# Principal.net
KiCad netlist of a schematic drawn in EAGLE
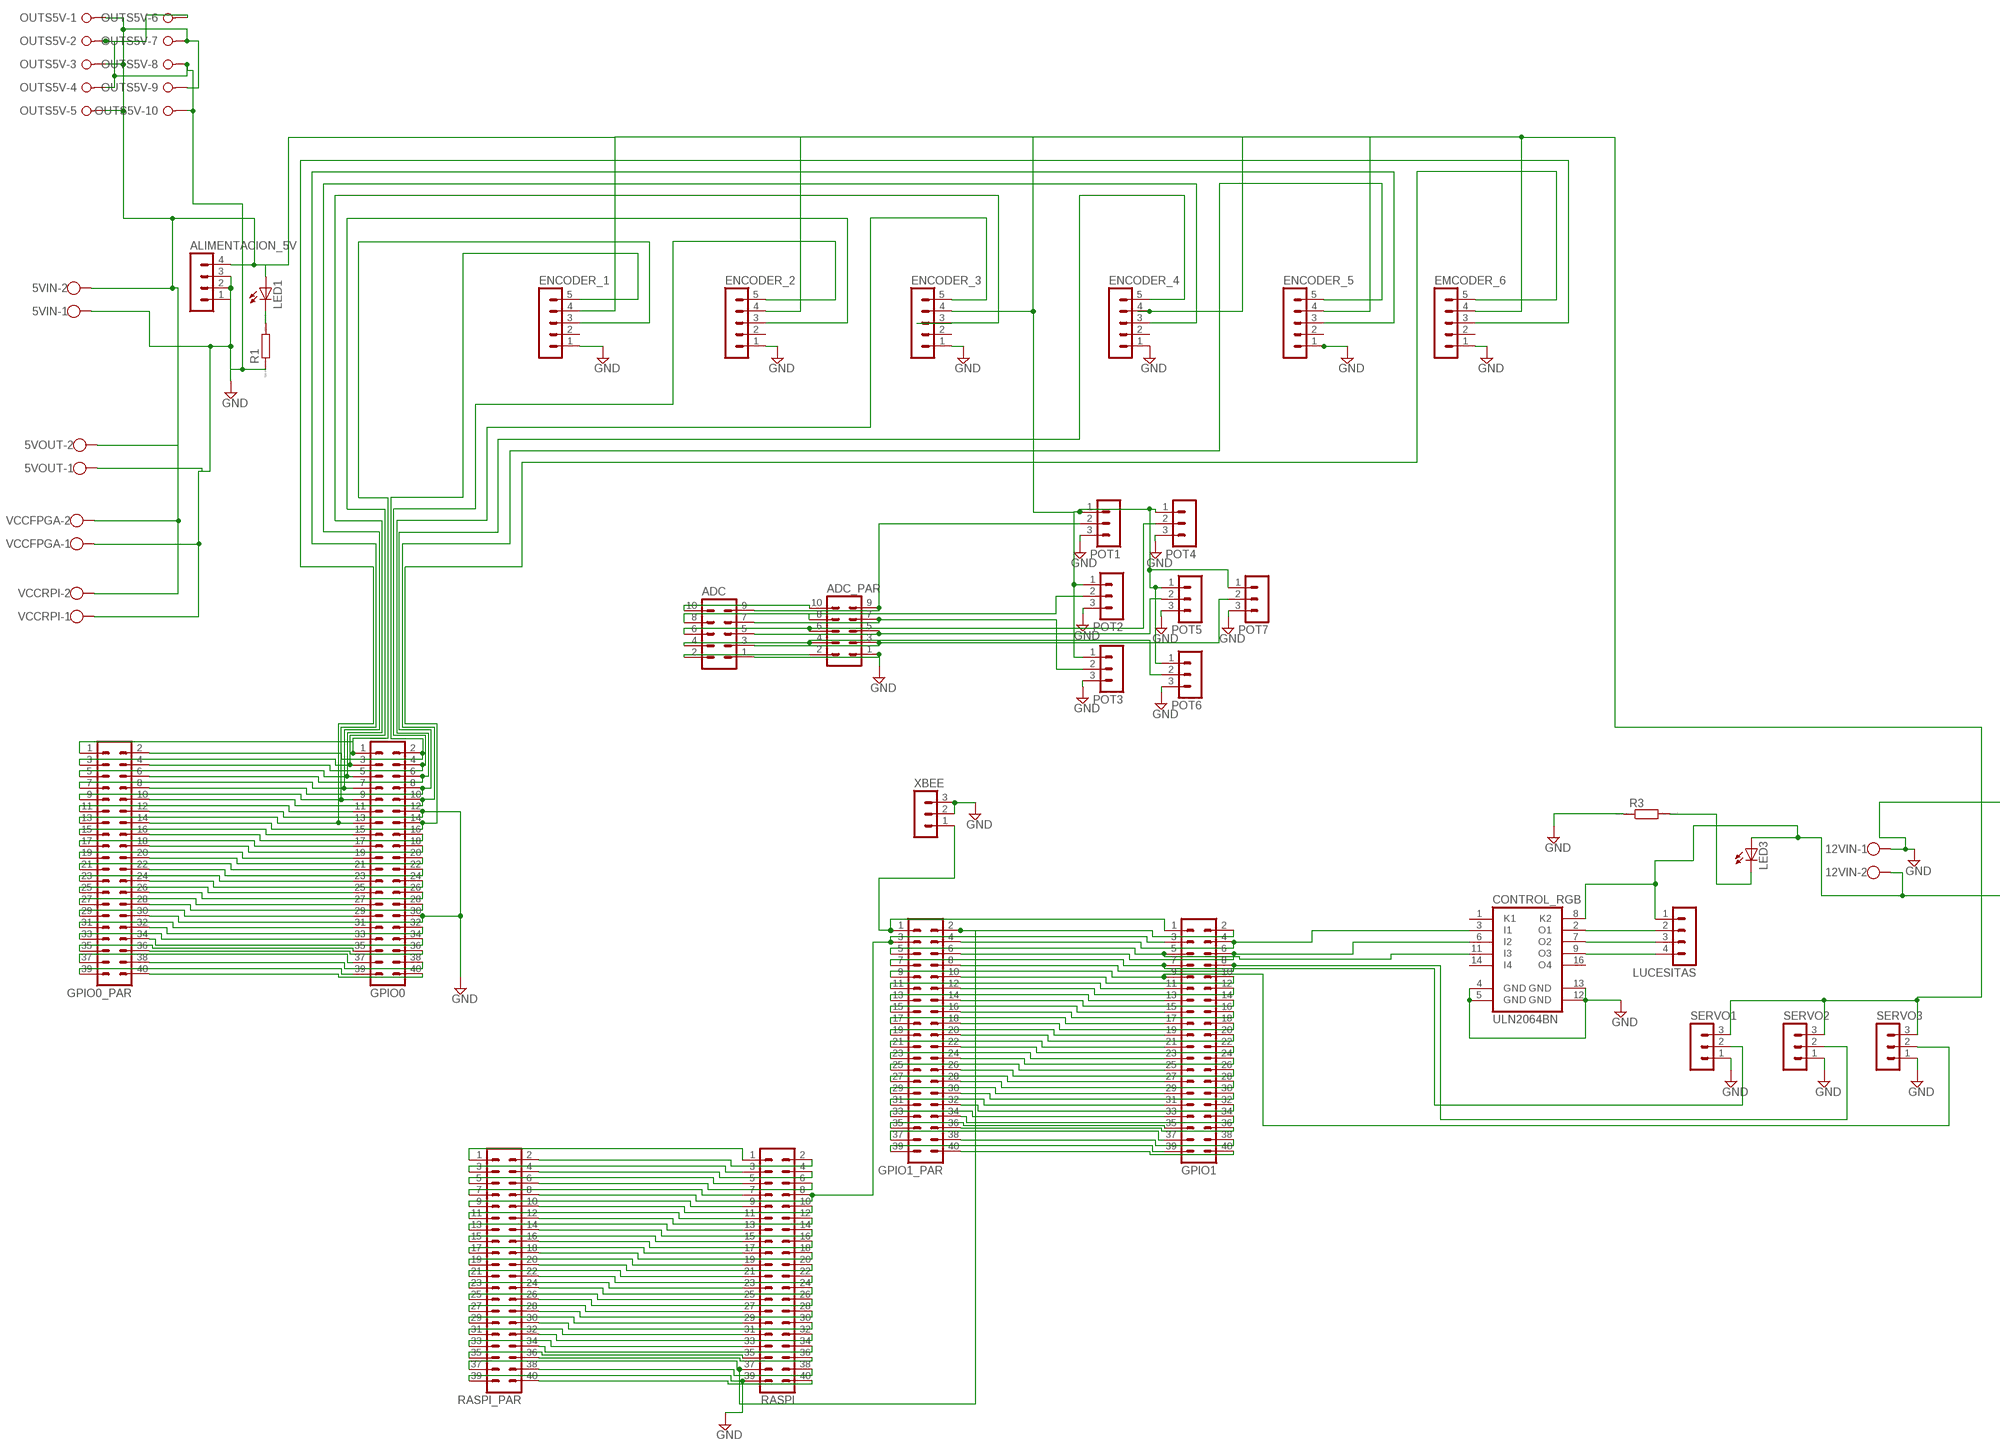
[diagram p0: schematic, sheet 1, part 1 of 2]
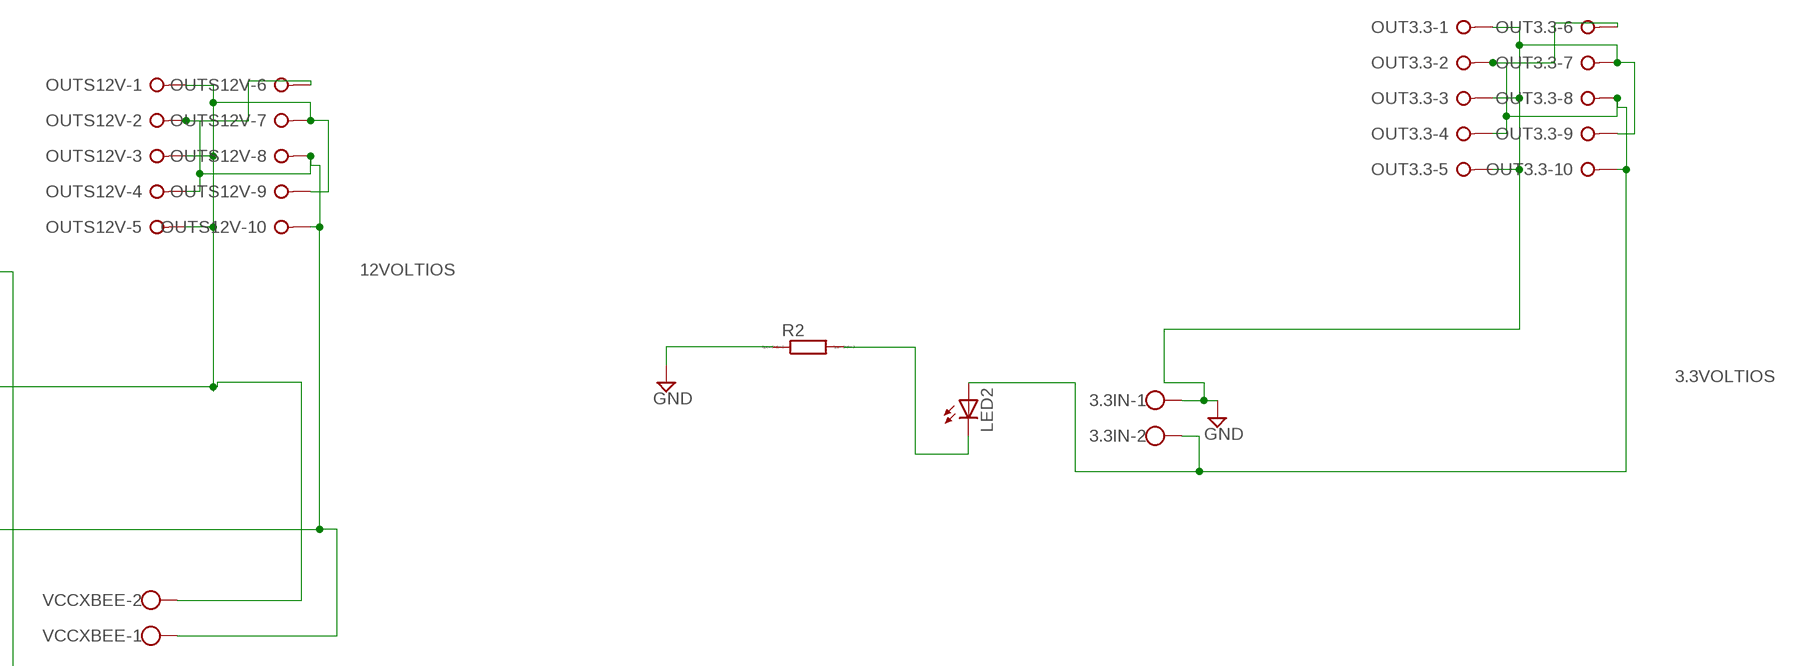
[diagram p1: schematic, sheet 1, part 2 of 2]

(export (version "E")
  (design (tool "Eeschema 10.0.6"))
  (components
    (comp (ref "3.3IN")
      (value "W237-102")
      (footprint "eagle-import:W237-102")
      (fields (field (name "MPN") "237-102"))
      (libsource (lib "eagle-import") (part "W237-102"))
    )
    (comp (ref "5VIN")
      (value "W237-102")
      (footprint "eagle-import:W237-102")
      (fields (field (name "MPN") "237-102"))
      (libsource (lib "eagle-import") (part "W237-102"))
    )
    (comp (ref "5VOUT")
      (value "W237-102")
      (footprint "eagle-import:W237-102")
      (fields (field (name "MPN") "237-102"))
      (libsource (lib "eagle-import") (part "W237-102"))
    )
    (comp (ref "12VIN")
      (value "W237-102")
      (footprint "eagle-import:W237-102")
      (fields (field (name "MPN") "237-102"))
      (libsource (lib "eagle-import") (part "W237-102"))
    )
    (comp (ref "ADC")
      (value "MA05-2")
      (footprint "eagle-import:MA05-2")
      (libsource (lib "eagle-import") (part "MA05-2"))
    )
    (comp (ref "ADC_PAR")
      (value "MA05-2")
      (footprint "eagle-import:MA05-2")
      (libsource (lib "eagle-import") (part "MA05-2"))
    )
    (comp (ref "ALIMENTACION_5V")
      (value "MA04-1")
      (footprint "eagle-import:MA04-1")
      (libsource (lib "eagle-import") (part "MA04-1"))
    )
    (comp (ref "CONTROL_RGB")
      (value "ULN2064BN")
      (footprint "eagle-import:DIL16")
      (libsource (lib "eagle-import") (part "ULN2064BN"))
    )
    (comp (ref "EMCODER_6")
      (value "MA05-1")
      (footprint "eagle-import:MA05-1")
      (libsource (lib "eagle-import") (part "MA05-1"))
    )
    (comp (ref "ENCODER_1")
      (value "MA05-1")
      (footprint "eagle-import:MA05-1")
      (libsource (lib "eagle-import") (part "MA05-1"))
    )
    (comp (ref "ENCODER_2")
      (value "MA05-1")
      (footprint "eagle-import:MA05-1")
      (libsource (lib "eagle-import") (part "MA05-1"))
    )
    (comp (ref "ENCODER_3")
      (value "MA05-1")
      (footprint "eagle-import:MA05-1")
      (libsource (lib "eagle-import") (part "MA05-1"))
    )
    (comp (ref "ENCODER_4")
      (value "MA05-1")
      (footprint "eagle-import:MA05-1")
      (libsource (lib "eagle-import") (part "MA05-1"))
    )
    (comp (ref "ENCODER_5")
      (value "MA05-1")
      (footprint "eagle-import:MA05-1")
      (libsource (lib "eagle-import") (part "MA05-1"))
    )
    (comp (ref "GPIO0")
      (value "MA20-2")
      (footprint "eagle-import:MA20-2")
      (libsource (lib "eagle-import") (part "MA20-2"))
    )
    (comp (ref "GPIO0_PAR")
      (value "MA20-2")
      (footprint "eagle-import:MA20-2")
      (libsource (lib "eagle-import") (part "MA20-2"))
    )
    (comp (ref "GPIO1")
      (value "MA20-2")
      (footprint "eagle-import:MA20-2")
      (libsource (lib "eagle-import") (part "MA20-2"))
    )
    (comp (ref "GPIO1_PAR")
      (value "MA20-2")
      (footprint "eagle-import:MA20-2")
      (libsource (lib "eagle-import") (part "MA20-2"))
    )
    (comp (ref "LED1")
      (value "LEDSML0805")
      (footprint "eagle-import:SML0805")
      (libsource (lib "eagle-import") (part "LEDSML0805"))
    )
    (comp (ref "LED2")
      (value "LEDSML0805")
      (footprint "eagle-import:SML0805")
      (libsource (lib "eagle-import") (part "LEDSML0805"))
    )
    (comp (ref "LED3")
      (value "LEDSML0805")
      (footprint "eagle-import:SML0805")
      (libsource (lib "eagle-import") (part "LEDSML0805"))
    )
    (comp (ref "LUCESITAS")
      (value "MA04-1")
      (footprint "eagle-import:MA04-1")
      (libsource (lib "eagle-import") (part "MA04-1"))
    )
    (comp (ref "OUT3.3")
      (value "W237-10P")
      (footprint "eagle-import:W237-10P")
      (libsource (lib "eagle-import") (part "W237-10P"))
    )
    (comp (ref "OUTS5V")
      (value "W237-10P")
      (footprint "eagle-import:W237-10P")
      (libsource (lib "eagle-import") (part "W237-10P"))
    )
    (comp (ref "OUTS12V")
      (value "W237-10P")
      (footprint "eagle-import:W237-10P")
      (libsource (lib "eagle-import") (part "W237-10P"))
    )
    (comp (ref "POT1")
      (value "MA03-1")
      (footprint "eagle-import:MA03-1")
      (libsource (lib "eagle-import") (part "MA03-1"))
    )
    (comp (ref "POT2")
      (value "MA03-1")
      (footprint "eagle-import:MA03-1")
      (libsource (lib "eagle-import") (part "MA03-1"))
    )
    (comp (ref "POT3")
      (value "MA03-1")
      (footprint "eagle-import:MA03-1")
      (libsource (lib "eagle-import") (part "MA03-1"))
    )
    (comp (ref "POT4")
      (value "MA03-1")
      (footprint "eagle-import:MA03-1")
      (libsource (lib "eagle-import") (part "MA03-1"))
    )
    (comp (ref "POT5")
      (value "MA03-1")
      (footprint "eagle-import:MA03-1")
      (libsource (lib "eagle-import") (part "MA03-1"))
    )
    (comp (ref "POT6")
      (value "MA03-1")
      (footprint "eagle-import:MA03-1")
      (libsource (lib "eagle-import") (part "MA03-1"))
    )
    (comp (ref "POT7")
      (value "MA03-1")
      (footprint "eagle-import:MA03-1")
      (libsource (lib "eagle-import") (part "MA03-1"))
    )
    (comp (ref "R1")
      (value "RR1206")
      (footprint "eagle-import:R1206")
      (libsource (lib "eagle-import") (part "RR1206"))
    )
    (comp (ref "R2")
      (value "RR1206")
      (footprint "eagle-import:R1206")
      (libsource (lib "eagle-import") (part "RR1206"))
    )
    (comp (ref "R3")
      (value "RR1206")
      (footprint "eagle-import:R1206")
      (libsource (lib "eagle-import") (part "RR1206"))
    )
    (comp (ref "RASPI")
      (value "MA20-2")
      (footprint "eagle-import:MA20-2")
      (libsource (lib "eagle-import") (part "MA20-2"))
    )
    (comp (ref "RASPI_PAR")
      (value "MA20-2")
      (footprint "eagle-import:MA20-2")
      (libsource (lib "eagle-import") (part "MA20-2"))
    )
    (comp (ref "SERVO1")
      (value "MA03-1")
      (footprint "eagle-import:MA03-1")
      (libsource (lib "eagle-import") (part "MA03-1"))
    )
    (comp (ref "SERVO2")
      (value "MA03-1")
      (footprint "eagle-import:MA03-1")
      (libsource (lib "eagle-import") (part "MA03-1"))
    )
    (comp (ref "SERVO3")
      (value "MA03-1")
      (footprint "eagle-import:MA03-1")
      (libsource (lib "eagle-import") (part "MA03-1"))
    )
    (comp (ref "VCCFPGA")
      (value "W237-102")
      (footprint "eagle-import:W237-102")
      (fields (field (name "MPN") "237-102"))
      (libsource (lib "eagle-import") (part "W237-102"))
    )
    (comp (ref "VCCRPI")
      (value "W237-102")
      (footprint "eagle-import:W237-102")
      (fields (field (name "MPN") "237-102"))
      (libsource (lib "eagle-import") (part "W237-102"))
    )
    (comp (ref "VCCXBEE")
      (value "W237-102")
      (footprint "eagle-import:W237-102")
      (fields (field (name "MPN") "237-102"))
      (libsource (lib "eagle-import") (part "W237-102"))
    )
    (comp (ref "XBEE")
      (value "MA03-1")
      (footprint "eagle-import:MA03-1")
      (libsource (lib "eagle-import") (part "MA03-1"))
    )
  )
  (nets
    (net (code "1") (name "/3.3VOLTIOS") (class "Default")
      (node (ref "3.3IN") (pin "2") (pinfunction "KL_2") (pintype "passive"))
      (node (ref "LED2") (pin "A") (pinfunction "A_A") (pintype "passive"))
      (node (ref "OUT3.3") (pin "10") (pinfunction "KL_10") (pintype "passive"))
      (node (ref "OUT3.3") (pin "2") (pinfunction "KL_2") (pintype "passive"))
      (node (ref "OUT3.3") (pin "4") (pinfunction "KL_4") (pintype "passive"))
      (node (ref "OUT3.3") (pin "6") (pinfunction "KL_6") (pintype "passive"))
      (node (ref "OUT3.3") (pin "8") (pinfunction "KL_8") (pintype "passive"))
    )
    (net (code "2") (name "/12VOLTIOS") (class "Default")
      (node (ref "12VIN") (pin "2") (pinfunction "KL_2") (pintype "passive"))
      (node (ref "CONTROL_RGB") (pin "8") (pinfunction "K2_8") (pintype "passive"))
      (node (ref "LED3") (pin "A") (pinfunction "A_A") (pintype "passive"))
      (node (ref "LUCESITAS") (pin "1") (pinfunction "1_1") (pintype "passive"))
      (node (ref "OUTS12V") (pin "10") (pinfunction "KL_10") (pintype "passive"))
      (node (ref "OUTS12V") (pin "2") (pinfunction "KL_2") (pintype "passive"))
      (node (ref "OUTS12V") (pin "4") (pinfunction "KL_4") (pintype "passive"))
      (node (ref "OUTS12V") (pin "6") (pinfunction "KL_6") (pintype "passive"))
      (node (ref "OUTS12V") (pin "8") (pinfunction "KL_8") (pintype "passive"))
      (node (ref "VCCXBEE") (pin "1") (pinfunction "KL_1") (pintype "passive"))
    )
    (net (code "3") (name "GND") (class "Default")
      (node (ref "12VIN") (pin "1") (pinfunction "KL_1") (pintype "passive"))
      (node (ref "3.3IN") (pin "1") (pinfunction "KL_1") (pintype "passive"))
      (node (ref "5VIN") (pin "1") (pinfunction "KL_1") (pintype "passive"))
      (node (ref "5VOUT") (pin "1") (pinfunction "KL_1") (pintype "passive"))
      (node (ref "ADC") (pin "1") (pinfunction "1_1") (pintype "passive"))
      (node (ref "ADC_PAR") (pin "1") (pinfunction "1_1") (pintype "passive"))
      (node (ref "ALIMENTACION_5V") (pin "1") (pinfunction "1_1") (pintype "passive"))
      (node (ref "ALIMENTACION_5V") (pin "2") (pinfunction "2_2") (pintype "passive"))
      (node (ref "ALIMENTACION_5V") (pin "3") (pinfunction "3_3") (pintype "passive"))
      (node (ref "CONTROL_RGB") (pin "12") (pinfunction "GND_12") (pintype "power_in"))
      (node (ref "CONTROL_RGB") (pin "13") (pinfunction "GND_13") (pintype "power_in"))
      (node (ref "CONTROL_RGB") (pin "4") (pinfunction "GND_4") (pintype "power_in"))
      (node (ref "CONTROL_RGB") (pin "5") (pinfunction "GND_5") (pintype "power_in"))
      (node (ref "EMCODER_6") (pin "1") (pinfunction "1_1") (pintype "passive"))
      (node (ref "ENCODER_1") (pin "1") (pinfunction "1_1") (pintype "passive"))
      (node (ref "ENCODER_2") (pin "1") (pinfunction "1_1") (pintype "passive"))
      (node (ref "ENCODER_3") (pin "1") (pinfunction "1_1") (pintype "passive"))
      (node (ref "ENCODER_4") (pin "1") (pinfunction "1_1") (pintype "passive"))
      (node (ref "ENCODER_5") (pin "1") (pinfunction "1_1") (pintype "passive"))
      (node (ref "GPIO0") (pin "12") (pinfunction "12_12") (pintype "passive"))
      (node (ref "GPIO0") (pin "30") (pinfunction "30_30") (pintype "passive"))
      (node (ref "GPIO0_PAR") (pin "12") (pinfunction "12_12") (pintype "passive"))
      (node (ref "GPIO0_PAR") (pin "30") (pinfunction "30_30") (pintype "passive"))
      (node (ref "OUT3.3") (pin "1") (pinfunction "KL_1") (pintype "passive"))
      (node (ref "OUT3.3") (pin "3") (pinfunction "KL_3") (pintype "passive"))
      (node (ref "OUT3.3") (pin "5") (pinfunction "KL_5") (pintype "passive"))
      (node (ref "OUT3.3") (pin "7") (pinfunction "KL_7") (pintype "passive"))
      (node (ref "OUT3.3") (pin "9") (pinfunction "KL_9") (pintype "passive"))
      (node (ref "OUTS12V") (pin "1") (pinfunction "KL_1") (pintype "passive"))
      (node (ref "OUTS12V") (pin "3") (pinfunction "KL_3") (pintype "passive"))
      (node (ref "OUTS12V") (pin "5") (pinfunction "KL_5") (pintype "passive"))
      (node (ref "OUTS12V") (pin "7") (pinfunction "KL_7") (pintype "passive"))
      (node (ref "OUTS12V") (pin "9") (pinfunction "KL_9") (pintype "passive"))
      (node (ref "OUTS5V") (pin "10") (pinfunction "KL_10") (pintype "passive"))
      (node (ref "OUTS5V") (pin "2") (pinfunction "KL_2") (pintype "passive"))
      (node (ref "OUTS5V") (pin "4") (pinfunction "KL_4") (pintype "passive"))
      (node (ref "OUTS5V") (pin "6") (pinfunction "KL_6") (pintype "passive"))
      (node (ref "OUTS5V") (pin "8") (pinfunction "KL_8") (pintype "passive"))
      (node (ref "POT1") (pin "3") (pinfunction "3_3") (pintype "passive"))
      (node (ref "POT2") (pin "3") (pinfunction "3_3") (pintype "passive"))
      (node (ref "POT3") (pin "3") (pinfunction "3_3") (pintype "passive"))
      (node (ref "POT4") (pin "3") (pinfunction "3_3") (pintype "passive"))
      (node (ref "POT5") (pin "3") (pinfunction "3_3") (pintype "passive"))
      (node (ref "POT6") (pin "3") (pinfunction "3_3") (pintype "passive"))
      (node (ref "POT7") (pin "3") (pinfunction "3_3") (pintype "passive"))
      (node (ref "R1") (pin "1") (pinfunction "1_1") (pintype "passive"))
      (node (ref "R2") (pin "1") (pinfunction "1_1") (pintype "passive"))
      (node (ref "R3") (pin "1") (pinfunction "1_1") (pintype "passive"))
      (node (ref "RASPI") (pin "39") (pinfunction "39_39") (pintype "passive"))
      (node (ref "RASPI_PAR") (pin "39") (pinfunction "39_39") (pintype "passive"))
      (node (ref "SERVO1") (pin "1") (pinfunction "1_1") (pintype "passive"))
      (node (ref "SERVO2") (pin "1") (pinfunction "1_1") (pintype "passive"))
      (node (ref "SERVO3") (pin "1") (pinfunction "1_1") (pintype "passive"))
      (node (ref "VCCFPGA") (pin "1") (pinfunction "KL_1") (pintype "passive"))
      (node (ref "VCCRPI") (pin "1") (pinfunction "KL_1") (pintype "passive"))
      (node (ref "VCCXBEE") (pin "2") (pinfunction "KL_2") (pintype "passive"))
      (node (ref "XBEE") (pin "2") (pinfunction "2_2") (pintype "passive"))
      (node (ref "XBEE") (pin "3") (pinfunction "3_3") (pintype "passive"))
    )
    (net (code "4") (name "Net-(5VINB-KL)") (class "Default")
      (node (ref "5VIN") (pin "2") (pinfunction "KL_2") (pintype "passive"))
      (node (ref "5VOUT") (pin "2") (pinfunction "KL_2") (pintype "passive"))
      (node (ref "ALIMENTACION_5V") (pin "4") (pinfunction "4_4") (pintype "passive"))
      (node (ref "EMCODER_6") (pin "4") (pinfunction "4_4") (pintype "passive"))
      (node (ref "ENCODER_1") (pin "4") (pinfunction "4_4") (pintype "passive"))
      (node (ref "ENCODER_2") (pin "4") (pinfunction "4_4") (pintype "passive"))
      (node (ref "ENCODER_3") (pin "4") (pinfunction "4_4") (pintype "passive"))
      (node (ref "ENCODER_4") (pin "4") (pinfunction "4_4") (pintype "passive"))
      (node (ref "ENCODER_5") (pin "4") (pinfunction "4_4") (pintype "passive"))
      (node (ref "LED1") (pin "A") (pinfunction "A_A") (pintype "passive"))
      (node (ref "OUTS5V") (pin "1") (pinfunction "KL_1") (pintype "passive"))
      (node (ref "OUTS5V") (pin "3") (pinfunction "KL_3") (pintype "passive"))
      (node (ref "OUTS5V") (pin "5") (pinfunction "KL_5") (pintype "passive"))
      (node (ref "OUTS5V") (pin "7") (pinfunction "KL_7") (pintype "passive"))
      (node (ref "OUTS5V") (pin "9") (pinfunction "KL_9") (pintype "passive"))
      (node (ref "POT1") (pin "1") (pinfunction "1_1") (pintype "passive"))
      (node (ref "POT2") (pin "1") (pinfunction "1_1") (pintype "passive"))
      (node (ref "POT3") (pin "1") (pinfunction "1_1") (pintype "passive"))
      (node (ref "POT4") (pin "1") (pinfunction "1_1") (pintype "passive"))
      (node (ref "POT5") (pin "1") (pinfunction "1_1") (pintype "passive"))
      (node (ref "POT6") (pin "1") (pinfunction "1_1") (pintype "passive"))
      (node (ref "POT7") (pin "1") (pinfunction "1_1") (pintype "passive"))
      (node (ref "SERVO1") (pin "3") (pinfunction "3_3") (pintype "passive"))
      (node (ref "SERVO2") (pin "3") (pinfunction "3_3") (pintype "passive"))
      (node (ref "SERVO3") (pin "3") (pinfunction "3_3") (pintype "passive"))
      (node (ref "VCCFPGA") (pin "2") (pinfunction "KL_2") (pintype "passive"))
      (node (ref "VCCRPI") (pin "2") (pinfunction "KL_2") (pintype "passive"))
    )
    (net (code "5") (name "Net-(ADC-Pad2)") (class "Default")
      (node (ref "ADC") (pin "2") (pinfunction "2_2") (pintype "passive"))
      (node (ref "ADC_PAR") (pin "2") (pinfunction "2_2") (pintype "passive"))
    )
    (net (code "6") (name "Net-(ADC-Pad3)") (class "Default")
      (node (ref "ADC") (pin "3") (pinfunction "3_3") (pintype "passive"))
      (node (ref "ADC_PAR") (pin "3") (pinfunction "3_3") (pintype "passive"))
      (node (ref "POT7") (pin "2") (pinfunction "2_2") (pintype "passive"))
    )
    (net (code "7") (name "Net-(ADC-Pad4)") (class "Default")
      (node (ref "ADC") (pin "4") (pinfunction "4_4") (pintype "passive"))
      (node (ref "ADC_PAR") (pin "4") (pinfunction "4_4") (pintype "passive"))
      (node (ref "POT6") (pin "2") (pinfunction "2_2") (pintype "passive"))
    )
    (net (code "8") (name "Net-(ADC-Pad5)") (class "Default")
      (node (ref "ADC") (pin "5") (pinfunction "5_5") (pintype "passive"))
      (node (ref "ADC_PAR") (pin "5") (pinfunction "5_5") (pintype "passive"))
      (node (ref "POT5") (pin "2") (pinfunction "2_2") (pintype "passive"))
    )
    (net (code "9") (name "Net-(ADC-Pad6)") (class "Default")
      (node (ref "ADC") (pin "6") (pinfunction "6_6") (pintype "passive"))
      (node (ref "ADC_PAR") (pin "6") (pinfunction "6_6") (pintype "passive"))
      (node (ref "POT4") (pin "2") (pinfunction "2_2") (pintype "passive"))
    )
    (net (code "10") (name "Net-(ADC-Pad7)") (class "Default")
      (node (ref "ADC") (pin "7") (pinfunction "7_7") (pintype "passive"))
      (node (ref "ADC_PAR") (pin "7") (pinfunction "7_7") (pintype "passive"))
      (node (ref "POT3") (pin "2") (pinfunction "2_2") (pintype "passive"))
    )
    (net (code "11") (name "Net-(ADC-Pad8)") (class "Default")
      (node (ref "ADC") (pin "8") (pinfunction "8_8") (pintype "passive"))
      (node (ref "ADC_PAR") (pin "8") (pinfunction "8_8") (pintype "passive"))
      (node (ref "POT2") (pin "2") (pinfunction "2_2") (pintype "passive"))
    )
    (net (code "12") (name "Net-(ADC-Pad9)") (class "Default")
      (node (ref "ADC") (pin "9") (pinfunction "9_9") (pintype "passive"))
      (node (ref "ADC_PAR") (pin "9") (pinfunction "9_9") (pintype "passive"))
      (node (ref "POT1") (pin "2") (pinfunction "2_2") (pintype "passive"))
    )
    (net (code "13") (name "Net-(ADC-Pad10)") (class "Default")
      (node (ref "ADC") (pin "10") (pinfunction "10_10") (pintype "passive"))
      (node (ref "ADC_PAR") (pin "10") (pinfunction "10_10") (pintype "passive"))
    )
    (net (code "14") (name "Net-(CONTROL_RGB-I1)") (class "Default")
      (node (ref "CONTROL_RGB") (pin "3") (pinfunction "I1_3") (pintype "input"))
      (node (ref "GPIO1") (pin "4") (pinfunction "4_4") (pintype "passive"))
      (node (ref "GPIO1_PAR") (pin "4") (pinfunction "4_4") (pintype "passive"))
    )
    (net (code "15") (name "Net-(CONTROL_RGB-I2)") (class "Default")
      (node (ref "CONTROL_RGB") (pin "6") (pinfunction "I2_6") (pintype "input"))
      (node (ref "GPIO1") (pin "6") (pinfunction "6_6") (pintype "passive"))
      (node (ref "GPIO1_PAR") (pin "6") (pinfunction "6_6") (pintype "passive"))
    )
    (net (code "16") (name "Net-(CONTROL_RGB-I3)") (class "Default")
      (node (ref "CONTROL_RGB") (pin "11") (pinfunction "I3_11") (pintype "input"))
      (node (ref "GPIO1") (pin "5") (pinfunction "5_5") (pintype "passive"))
      (node (ref "GPIO1_PAR") (pin "5") (pinfunction "5_5") (pintype "passive"))
    )
    (net (code "17") (name "Net-(CONTROL_RGB-O1)") (class "Default")
      (node (ref "CONTROL_RGB") (pin "2") (pinfunction "O1_2") (pintype "open_collector"))
      (node (ref "LUCESITAS") (pin "2") (pinfunction "2_2") (pintype "passive"))
    )
    (net (code "18") (name "Net-(CONTROL_RGB-O2)") (class "Default")
      (node (ref "CONTROL_RGB") (pin "7") (pinfunction "O2_7") (pintype "open_collector"))
      (node (ref "LUCESITAS") (pin "3") (pinfunction "3_3") (pintype "passive"))
    )
    (net (code "19") (name "Net-(CONTROL_RGB-O3)") (class "Default")
      (node (ref "CONTROL_RGB") (pin "9") (pinfunction "O3_9") (pintype "open_collector"))
      (node (ref "LUCESITAS") (pin "4") (pinfunction "4_4") (pintype "passive"))
    )
    (net (code "20") (name "Net-(EMCODER_6-Pad3)") (class "Default")
      (node (ref "EMCODER_6") (pin "3") (pinfunction "3_3") (pintype "passive"))
      (node (ref "GPIO0") (pin "13") (pinfunction "13_13") (pintype "passive"))
      (node (ref "GPIO0_PAR") (pin "13") (pinfunction "13_13") (pintype "passive"))
    )
    (net (code "21") (name "Net-(EMCODER_6-Pad5)") (class "Default")
      (node (ref "EMCODER_6") (pin "5") (pinfunction "5_5") (pintype "passive"))
      (node (ref "GPIO0") (pin "14") (pinfunction "14_14") (pintype "passive"))
      (node (ref "GPIO0_PAR") (pin "14") (pinfunction "14_14") (pintype "passive"))
    )
    (net (code "22") (name "Net-(ENCODER_1-Pad3)") (class "Default")
      (node (ref "ENCODER_1") (pin "3") (pinfunction "3_3") (pintype "passive"))
      (node (ref "GPIO0") (pin "1") (pinfunction "1_1") (pintype "passive"))
      (node (ref "GPIO0_PAR") (pin "1") (pinfunction "1_1") (pintype "passive"))
    )
    (net (code "23") (name "Net-(ENCODER_1-Pad5)") (class "Default")
      (node (ref "ENCODER_1") (pin "5") (pinfunction "5_5") (pintype "passive"))
      (node (ref "GPIO0") (pin "2") (pinfunction "2_2") (pintype "passive"))
      (node (ref "GPIO0_PAR") (pin "2") (pinfunction "2_2") (pintype "passive"))
    )
    (net (code "24") (name "Net-(ENCODER_2-Pad3)") (class "Default")
      (node (ref "ENCODER_2") (pin "3") (pinfunction "3_3") (pintype "passive"))
      (node (ref "GPIO0") (pin "3") (pinfunction "3_3") (pintype "passive"))
      (node (ref "GPIO0_PAR") (pin "3") (pinfunction "3_3") (pintype "passive"))
    )
    (net (code "25") (name "Net-(ENCODER_2-Pad5)") (class "Default")
      (node (ref "ENCODER_2") (pin "5") (pinfunction "5_5") (pintype "passive"))
      (node (ref "GPIO0") (pin "4") (pinfunction "4_4") (pintype "passive"))
      (node (ref "GPIO0_PAR") (pin "4") (pinfunction "4_4") (pintype "passive"))
    )
    (net (code "26") (name "Net-(ENCODER_3-Pad3)") (class "Default")
      (node (ref "ENCODER_3") (pin "3") (pinfunction "3_3") (pintype "passive"))
      (node (ref "GPIO0") (pin "5") (pinfunction "5_5") (pintype "passive"))
      (node (ref "GPIO0_PAR") (pin "5") (pinfunction "5_5") (pintype "passive"))
    )
    (net (code "27") (name "Net-(ENCODER_3-Pad5)") (class "Default")
      (node (ref "ENCODER_3") (pin "5") (pinfunction "5_5") (pintype "passive"))
      (node (ref "GPIO0") (pin "6") (pinfunction "6_6") (pintype "passive"))
      (node (ref "GPIO0_PAR") (pin "6") (pinfunction "6_6") (pintype "passive"))
    )
    (net (code "28") (name "Net-(ENCODER_4-Pad3)") (class "Default")
      (node (ref "ENCODER_4") (pin "3") (pinfunction "3_3") (pintype "passive"))
      (node (ref "GPIO0") (pin "7") (pinfunction "7_7") (pintype "passive"))
      (node (ref "GPIO0_PAR") (pin "7") (pinfunction "7_7") (pintype "passive"))
    )
    (net (code "29") (name "Net-(ENCODER_4-Pad5)") (class "Default")
      (node (ref "ENCODER_4") (pin "5") (pinfunction "5_5") (pintype "passive"))
      (node (ref "GPIO0") (pin "8") (pinfunction "8_8") (pintype "passive"))
      (node (ref "GPIO0_PAR") (pin "8") (pinfunction "8_8") (pintype "passive"))
    )
    (net (code "30") (name "Net-(ENCODER_5-Pad3)") (class "Default")
      (node (ref "ENCODER_5") (pin "3") (pinfunction "3_3") (pintype "passive"))
      (node (ref "GPIO0") (pin "9") (pinfunction "9_9") (pintype "passive"))
      (node (ref "GPIO0_PAR") (pin "9") (pinfunction "9_9") (pintype "passive"))
    )
    (net (code "31") (name "Net-(ENCODER_5-Pad5)") (class "Default")
      (node (ref "ENCODER_5") (pin "5") (pinfunction "5_5") (pintype "passive"))
      (node (ref "GPIO0") (pin "10") (pinfunction "10_10") (pintype "passive"))
      (node (ref "GPIO0_PAR") (pin "10") (pinfunction "10_10") (pintype "passive"))
    )
    (net (code "32") (name "Net-(GPIO0-Pad11)") (class "Default")
      (node (ref "GPIO0") (pin "11") (pinfunction "11_11") (pintype "passive"))
      (node (ref "GPIO0_PAR") (pin "11") (pinfunction "11_11") (pintype "passive"))
    )
    (net (code "33") (name "Net-(GPIO0-Pad15)") (class "Default")
      (node (ref "GPIO0") (pin "15") (pinfunction "15_15") (pintype "passive"))
      (node (ref "GPIO0_PAR") (pin "15") (pinfunction "15_15") (pintype "passive"))
    )
    (net (code "34") (name "Net-(GPIO0-Pad16)") (class "Default")
      (node (ref "GPIO0") (pin "16") (pinfunction "16_16") (pintype "passive"))
      (node (ref "GPIO0_PAR") (pin "16") (pinfunction "16_16") (pintype "passive"))
    )
    (net (code "35") (name "Net-(GPIO0-Pad17)") (class "Default")
      (node (ref "GPIO0") (pin "17") (pinfunction "17_17") (pintype "passive"))
      (node (ref "GPIO0_PAR") (pin "17") (pinfunction "17_17") (pintype "passive"))
    )
    (net (code "36") (name "Net-(GPIO0-Pad18)") (class "Default")
      (node (ref "GPIO0") (pin "18") (pinfunction "18_18") (pintype "passive"))
      (node (ref "GPIO0_PAR") (pin "18") (pinfunction "18_18") (pintype "passive"))
    )
    (net (code "37") (name "Net-(GPIO0-Pad19)") (class "Default")
      (node (ref "GPIO0") (pin "19") (pinfunction "19_19") (pintype "passive"))
      (node (ref "GPIO0_PAR") (pin "19") (pinfunction "19_19") (pintype "passive"))
    )
    (net (code "38") (name "Net-(GPIO0-Pad20)") (class "Default")
      (node (ref "GPIO0") (pin "20") (pinfunction "20_20") (pintype "passive"))
      (node (ref "GPIO0_PAR") (pin "20") (pinfunction "20_20") (pintype "passive"))
    )
    (net (code "39") (name "Net-(GPIO0-Pad21)") (class "Default")
      (node (ref "GPIO0") (pin "21") (pinfunction "21_21") (pintype "passive"))
      (node (ref "GPIO0_PAR") (pin "21") (pinfunction "21_21") (pintype "passive"))
    )
    (net (code "40") (name "Net-(GPIO0-Pad22)") (class "Default")
      (node (ref "GPIO0") (pin "22") (pinfunction "22_22") (pintype "passive"))
      (node (ref "GPIO0_PAR") (pin "22") (pinfunction "22_22") (pintype "passive"))
    )
    (net (code "41") (name "Net-(GPIO0-Pad23)") (class "Default")
      (node (ref "GPIO0") (pin "23") (pinfunction "23_23") (pintype "passive"))
      (node (ref "GPIO0_PAR") (pin "23") (pinfunction "23_23") (pintype "passive"))
    )
    (net (code "42") (name "Net-(GPIO0-Pad24)") (class "Default")
      (node (ref "GPIO0") (pin "24") (pinfunction "24_24") (pintype "passive"))
      (node (ref "GPIO0_PAR") (pin "24") (pinfunction "24_24") (pintype "passive"))
    )
    (net (code "43") (name "Net-(GPIO0-Pad25)") (class "Default")
      (node (ref "GPIO0") (pin "25") (pinfunction "25_25") (pintype "passive"))
      (node (ref "GPIO0_PAR") (pin "25") (pinfunction "25_25") (pintype "passive"))
    )
    (net (code "44") (name "Net-(GPIO0-Pad26)") (class "Default")
      (node (ref "GPIO0") (pin "26") (pinfunction "26_26") (pintype "passive"))
      (node (ref "GPIO0_PAR") (pin "26") (pinfunction "26_26") (pintype "passive"))
    )
    (net (code "45") (name "Net-(GPIO0-Pad27)") (class "Default")
      (node (ref "GPIO0") (pin "27") (pinfunction "27_27") (pintype "passive"))
      (node (ref "GPIO0_PAR") (pin "27") (pinfunction "27_27") (pintype "passive"))
    )
    (net (code "46") (name "Net-(GPIO0-Pad28)") (class "Default")
      (node (ref "GPIO0") (pin "28") (pinfunction "28_28") (pintype "passive"))
      (node (ref "GPIO0_PAR") (pin "28") (pinfunction "28_28") (pintype "passive"))
    )
    (net (code "47") (name "Net-(GPIO0-Pad29)") (class "Default")
      (node (ref "GPIO0") (pin "29") (pinfunction "29_29") (pintype "passive"))
      (node (ref "GPIO0_PAR") (pin "29") (pinfunction "29_29") (pintype "passive"))
    )
    (net (code "48") (name "Net-(GPIO0-Pad31)") (class "Default")
      (node (ref "GPIO0") (pin "31") (pinfunction "31_31") (pintype "passive"))
      (node (ref "GPIO0_PAR") (pin "31") (pinfunction "31_31") (pintype "passive"))
    )
    (net (code "49") (name "Net-(GPIO0-Pad32)") (class "Default")
      (node (ref "GPIO0") (pin "32") (pinfunction "32_32") (pintype "passive"))
      (node (ref "GPIO0_PAR") (pin "32") (pinfunction "32_32") (pintype "passive"))
    )
    (net (code "50") (name "Net-(GPIO0-Pad33)") (class "Default")
      (node (ref "GPIO0") (pin "33") (pinfunction "33_33") (pintype "passive"))
      (node (ref "GPIO0_PAR") (pin "33") (pinfunction "33_33") (pintype "passive"))
    )
    (net (code "51") (name "Net-(GPIO0-Pad34)") (class "Default")
      (node (ref "GPIO0") (pin "34") (pinfunction "34_34") (pintype "passive"))
      (node (ref "GPIO0_PAR") (pin "34") (pinfunction "34_34") (pintype "passive"))
    )
    (net (code "52") (name "Net-(GPIO0-Pad35)") (class "Default")
      (node (ref "GPIO0") (pin "35") (pinfunction "35_35") (pintype "passive"))
      (node (ref "GPIO0_PAR") (pin "35") (pinfunction "35_35") (pintype "passive"))
    )
    (net (code "53") (name "Net-(GPIO0-Pad36)") (class "Default")
      (node (ref "GPIO0") (pin "36") (pinfunction "36_36") (pintype "passive"))
      (node (ref "GPIO0_PAR") (pin "36") (pinfunction "36_36") (pintype "passive"))
    )
    (net (code "54") (name "Net-(GPIO0-Pad37)") (class "Default")
      (node (ref "GPIO0") (pin "37") (pinfunction "37_37") (pintype "passive"))
      (node (ref "GPIO0_PAR") (pin "37") (pinfunction "37_37") (pintype "passive"))
    )
    (net (code "55") (name "Net-(GPIO0-Pad38)") (class "Default")
      (node (ref "GPIO0") (pin "38") (pinfunction "38_38") (pintype "passive"))
      (node (ref "GPIO0_PAR") (pin "38") (pinfunction "38_38") (pintype "passive"))
    )
    (net (code "56") (name "Net-(GPIO0-Pad39)") (class "Default")
      (node (ref "GPIO0") (pin "39") (pinfunction "39_39") (pintype "passive"))
      (node (ref "GPIO0_PAR") (pin "39") (pinfunction "39_39") (pintype "passive"))
    )
    (net (code "57") (name "Net-(GPIO0-Pad40)") (class "Default")
      (node (ref "GPIO0") (pin "40") (pinfunction "40_40") (pintype "passive"))
      (node (ref "GPIO0_PAR") (pin "40") (pinfunction "40_40") (pintype "passive"))
    )
    (net (code "58") (name "Net-(GPIO1-Pad1)") (class "Default")
      (node (ref "GPIO1") (pin "1") (pinfunction "1_1") (pintype "passive"))
      (node (ref "GPIO1_PAR") (pin "1") (pinfunction "1_1") (pintype "passive"))
      (node (ref "XBEE") (pin "1") (pinfunction "1_1") (pintype "passive"))
    )
    (net (code "59") (name "Net-(GPIO1-Pad2)") (class "Default")
      (node (ref "GPIO1") (pin "2") (pinfunction "2_2") (pintype "passive"))
      (node (ref "GPIO1_PAR") (pin "2") (pinfunction "2_2") (pintype "passive"))
      (node (ref "RASPI") (pin "37") (pinfunction "37_37") (pintype "passive"))
      (node (ref "RASPI_PAR") (pin "37") (pinfunction "37_37") (pintype "passive"))
    )
    (net (code "60") (name "Net-(GPIO1-Pad3)") (class "Default")
      (node (ref "GPIO1") (pin "3") (pinfunction "3_3") (pintype "passive"))
      (node (ref "GPIO1_PAR") (pin "3") (pinfunction "3_3") (pintype "passive"))
      (node (ref "RASPI") (pin "8") (pinfunction "8_8") (pintype "passive"))
      (node (ref "RASPI_PAR") (pin "8") (pinfunction "8_8") (pintype "passive"))
    )
    (net (code "61") (name "Net-(GPIO1-Pad7)") (class "Default")
      (node (ref "GPIO1") (pin "7") (pinfunction "7_7") (pintype "passive"))
      (node (ref "GPIO1_PAR") (pin "7") (pinfunction "7_7") (pintype "passive"))
      (node (ref "SERVO1") (pin "2") (pinfunction "2_2") (pintype "passive"))
    )
    (net (code "62") (name "Net-(GPIO1-Pad8)") (class "Default")
      (node (ref "GPIO1") (pin "8") (pinfunction "8_8") (pintype "passive"))
      (node (ref "GPIO1_PAR") (pin "8") (pinfunction "8_8") (pintype "passive"))
      (node (ref "SERVO2") (pin "2") (pinfunction "2_2") (pintype "passive"))
    )
    (net (code "63") (name "Net-(GPIO1-Pad9)") (class "Default")
      (node (ref "GPIO1") (pin "9") (pinfunction "9_9") (pintype "passive"))
      (node (ref "GPIO1_PAR") (pin "9") (pinfunction "9_9") (pintype "passive"))
      (node (ref "SERVO3") (pin "2") (pinfunction "2_2") (pintype "passive"))
    )
    (net (code "64") (name "Net-(GPIO1-Pad10)") (class "Default")
      (node (ref "GPIO1") (pin "10") (pinfunction "10_10") (pintype "passive"))
      (node (ref "GPIO1_PAR") (pin "10") (pinfunction "10_10") (pintype "passive"))
    )
    (net (code "65") (name "Net-(GPIO1-Pad11)") (class "Default")
      (node (ref "GPIO1") (pin "11") (pinfunction "11_11") (pintype "passive"))
      (node (ref "GPIO1_PAR") (pin "11") (pinfunction "11_11") (pintype "passive"))
    )
    (net (code "66") (name "Net-(GPIO1-Pad12)") (class "Default")
      (node (ref "GPIO1") (pin "12") (pinfunction "12_12") (pintype "passive"))
      (node (ref "GPIO1_PAR") (pin "12") (pinfunction "12_12") (pintype "passive"))
    )
    (net (code "67") (name "Net-(GPIO1-Pad13)") (class "Default")
      (node (ref "GPIO1") (pin "13") (pinfunction "13_13") (pintype "passive"))
      (node (ref "GPIO1_PAR") (pin "13") (pinfunction "13_13") (pintype "passive"))
    )
    (net (code "68") (name "Net-(GPIO1-Pad14)") (class "Default")
      (node (ref "GPIO1") (pin "14") (pinfunction "14_14") (pintype "passive"))
      (node (ref "GPIO1_PAR") (pin "14") (pinfunction "14_14") (pintype "passive"))
    )
    (net (code "69") (name "Net-(GPIO1-Pad15)") (class "Default")
      (node (ref "GPIO1") (pin "15") (pinfunction "15_15") (pintype "passive"))
      (node (ref "GPIO1_PAR") (pin "15") (pinfunction "15_15") (pintype "passive"))
    )
    (net (code "70") (name "Net-(GPIO1-Pad16)") (class "Default")
      (node (ref "GPIO1") (pin "16") (pinfunction "16_16") (pintype "passive"))
      (node (ref "GPIO1_PAR") (pin "16") (pinfunction "16_16") (pintype "passive"))
    )
    (net (code "71") (name "Net-(GPIO1-Pad17)") (class "Default")
      (node (ref "GPIO1") (pin "17") (pinfunction "17_17") (pintype "passive"))
      (node (ref "GPIO1_PAR") (pin "17") (pinfunction "17_17") (pintype "passive"))
    )
    (net (code "72") (name "Net-(GPIO1-Pad18)") (class "Default")
      (node (ref "GPIO1") (pin "18") (pinfunction "18_18") (pintype "passive"))
      (node (ref "GPIO1_PAR") (pin "18") (pinfunction "18_18") (pintype "passive"))
    )
    (net (code "73") (name "Net-(GPIO1-Pad19)") (class "Default")
      (node (ref "GPIO1") (pin "19") (pinfunction "19_19") (pintype "passive"))
      (node (ref "GPIO1_PAR") (pin "19") (pinfunction "19_19") (pintype "passive"))
    )
    (net (code "74") (name "Net-(GPIO1-Pad20)") (class "Default")
      (node (ref "GPIO1") (pin "20") (pinfunction "20_20") (pintype "passive"))
      (node (ref "GPIO1_PAR") (pin "20") (pinfunction "20_20") (pintype "passive"))
    )
    (net (code "75") (name "Net-(GPIO1-Pad21)") (class "Default")
      (node (ref "GPIO1") (pin "21") (pinfunction "21_21") (pintype "passive"))
      (node (ref "GPIO1_PAR") (pin "21") (pinfunction "21_21") (pintype "passive"))
    )
    (net (code "76") (name "Net-(GPIO1-Pad22)") (class "Default")
      (node (ref "GPIO1") (pin "22") (pinfunction "22_22") (pintype "passive"))
      (node (ref "GPIO1_PAR") (pin "22") (pinfunction "22_22") (pintype "passive"))
    )
    (net (code "77") (name "Net-(GPIO1-Pad23)") (class "Default")
      (node (ref "GPIO1") (pin "23") (pinfunction "23_23") (pintype "passive"))
      (node (ref "GPIO1_PAR") (pin "23") (pinfunction "23_23") (pintype "passive"))
    )
    (net (code "78") (name "Net-(GPIO1-Pad24)") (class "Default")
      (node (ref "GPIO1") (pin "24") (pinfunction "24_24") (pintype "passive"))
      (node (ref "GPIO1_PAR") (pin "24") (pinfunction "24_24") (pintype "passive"))
    )
    (net (code "79") (name "Net-(GPIO1-Pad25)") (class "Default")
      (node (ref "GPIO1") (pin "25") (pinfunction "25_25") (pintype "passive"))
      (node (ref "GPIO1_PAR") (pin "25") (pinfunction "25_25") (pintype "passive"))
    )
    (net (code "80") (name "Net-(GPIO1-Pad26)") (class "Default")
      (node (ref "GPIO1") (pin "26") (pinfunction "26_26") (pintype "passive"))
      (node (ref "GPIO1_PAR") (pin "26") (pinfunction "26_26") (pintype "passive"))
    )
    (net (code "81") (name "Net-(GPIO1-Pad27)") (class "Default")
      (node (ref "GPIO1") (pin "27") (pinfunction "27_27") (pintype "passive"))
      (node (ref "GPIO1_PAR") (pin "27") (pinfunction "27_27") (pintype "passive"))
    )
    (net (code "82") (name "Net-(GPIO1-Pad28)") (class "Default")
      (node (ref "GPIO1") (pin "28") (pinfunction "28_28") (pintype "passive"))
      (node (ref "GPIO1_PAR") (pin "28") (pinfunction "28_28") (pintype "passive"))
    )
    (net (code "83") (name "Net-(GPIO1-Pad29)") (class "Default")
      (node (ref "GPIO1") (pin "29") (pinfunction "29_29") (pintype "passive"))
      (node (ref "GPIO1_PAR") (pin "29") (pinfunction "29_29") (pintype "passive"))
    )
    (net (code "84") (name "Net-(GPIO1-Pad30)") (class "Default")
      (node (ref "GPIO1") (pin "30") (pinfunction "30_30") (pintype "passive"))
      (node (ref "GPIO1_PAR") (pin "30") (pinfunction "30_30") (pintype "passive"))
    )
    (net (code "85") (name "Net-(GPIO1-Pad31)") (class "Default")
      (node (ref "GPIO1") (pin "31") (pinfunction "31_31") (pintype "passive"))
      (node (ref "GPIO1_PAR") (pin "31") (pinfunction "31_31") (pintype "passive"))
    )
    (net (code "86") (name "Net-(GPIO1-Pad32)") (class "Default")
      (node (ref "GPIO1") (pin "32") (pinfunction "32_32") (pintype "passive"))
      (node (ref "GPIO1_PAR") (pin "32") (pinfunction "32_32") (pintype "passive"))
    )
    (net (code "87") (name "Net-(GPIO1-Pad33)") (class "Default")
      (node (ref "GPIO1") (pin "33") (pinfunction "33_33") (pintype "passive"))
      (node (ref "GPIO1_PAR") (pin "33") (pinfunction "33_33") (pintype "passive"))
    )
    (net (code "88") (name "Net-(GPIO1-Pad34)") (class "Default")
      (node (ref "GPIO1") (pin "34") (pinfunction "34_34") (pintype "passive"))
      (node (ref "GPIO1_PAR") (pin "34") (pinfunction "34_34") (pintype "passive"))
    )
    (net (code "89") (name "Net-(GPIO1-Pad35)") (class "Default")
      (node (ref "GPIO1") (pin "35") (pinfunction "35_35") (pintype "passive"))
      (node (ref "GPIO1_PAR") (pin "35") (pinfunction "35_35") (pintype "passive"))
    )
    (net (code "90") (name "Net-(GPIO1-Pad36)") (class "Default")
      (node (ref "GPIO1") (pin "36") (pinfunction "36_36") (pintype "passive"))
      (node (ref "GPIO1_PAR") (pin "36") (pinfunction "36_36") (pintype "passive"))
    )
    (net (code "91") (name "Net-(GPIO1-Pad37)") (class "Default")
      (node (ref "GPIO1") (pin "37") (pinfunction "37_37") (pintype "passive"))
      (node (ref "GPIO1_PAR") (pin "37") (pinfunction "37_37") (pintype "passive"))
    )
    (net (code "92") (name "Net-(GPIO1-Pad38)") (class "Default")
      (node (ref "GPIO1") (pin "38") (pinfunction "38_38") (pintype "passive"))
      (node (ref "GPIO1_PAR") (pin "38") (pinfunction "38_38") (pintype "passive"))
    )
    (net (code "93") (name "Net-(GPIO1-Pad39)") (class "Default")
      (node (ref "GPIO1") (pin "39") (pinfunction "39_39") (pintype "passive"))
      (node (ref "GPIO1_PAR") (pin "39") (pinfunction "39_39") (pintype "passive"))
    )
    (net (code "94") (name "Net-(GPIO1-Pad40)") (class "Default")
      (node (ref "GPIO1") (pin "40") (pinfunction "40_40") (pintype "passive"))
      (node (ref "GPIO1_PAR") (pin "40") (pinfunction "40_40") (pintype "passive"))
    )
    (net (code "95") (name "Net-(LED1-PadC)") (class "Default")
      (node (ref "LED1") (pin "C") (pinfunction "C_C") (pintype "passive"))
      (node (ref "R1") (pin "2") (pinfunction "2_2") (pintype "passive"))
    )
    (net (code "96") (name "Net-(LED2-PadC)") (class "Default")
      (node (ref "LED2") (pin "C") (pinfunction "C_C") (pintype "passive"))
      (node (ref "R2") (pin "2") (pinfunction "2_2") (pintype "passive"))
    )
    (net (code "97") (name "Net-(LED3-PadC)") (class "Default")
      (node (ref "LED3") (pin "C") (pinfunction "C_C") (pintype "passive"))
      (node (ref "R3") (pin "2") (pinfunction "2_2") (pintype "passive"))
    )
    (net (code "98") (name "Net-(RASPI-Pad1)") (class "Default")
      (node (ref "RASPI") (pin "1") (pinfunction "1_1") (pintype "passive"))
      (node (ref "RASPI_PAR") (pin "1") (pinfunction "1_1") (pintype "passive"))
    )
    (net (code "99") (name "Net-(RASPI-Pad2)") (class "Default")
      (node (ref "RASPI") (pin "2") (pinfunction "2_2") (pintype "passive"))
      (node (ref "RASPI_PAR") (pin "2") (pinfunction "2_2") (pintype "passive"))
    )
    (net (code "100") (name "Net-(RASPI-Pad3)") (class "Default")
      (node (ref "RASPI") (pin "3") (pinfunction "3_3") (pintype "passive"))
      (node (ref "RASPI_PAR") (pin "3") (pinfunction "3_3") (pintype "passive"))
    )
    (net (code "101") (name "Net-(RASPI-Pad4)") (class "Default")
      (node (ref "RASPI") (pin "4") (pinfunction "4_4") (pintype "passive"))
      (node (ref "RASPI_PAR") (pin "4") (pinfunction "4_4") (pintype "passive"))
    )
    (net (code "102") (name "Net-(RASPI-Pad5)") (class "Default")
      (node (ref "RASPI") (pin "5") (pinfunction "5_5") (pintype "passive"))
      (node (ref "RASPI_PAR") (pin "5") (pinfunction "5_5") (pintype "passive"))
    )
    (net (code "103") (name "Net-(RASPI-Pad6)") (class "Default")
      (node (ref "RASPI") (pin "6") (pinfunction "6_6") (pintype "passive"))
      (node (ref "RASPI_PAR") (pin "6") (pinfunction "6_6") (pintype "passive"))
    )
    (net (code "104") (name "Net-(RASPI-Pad7)") (class "Default")
      (node (ref "RASPI") (pin "7") (pinfunction "7_7") (pintype "passive"))
      (node (ref "RASPI_PAR") (pin "7") (pinfunction "7_7") (pintype "passive"))
    )
    (net (code "105") (name "Net-(RASPI-Pad9)") (class "Default")
      (node (ref "RASPI") (pin "9") (pinfunction "9_9") (pintype "passive"))
      (node (ref "RASPI_PAR") (pin "9") (pinfunction "9_9") (pintype "passive"))
    )
    (net (code "106") (name "Net-(RASPI-Pad10)") (class "Default")
      (node (ref "RASPI") (pin "10") (pinfunction "10_10") (pintype "passive"))
      (node (ref "RASPI_PAR") (pin "10") (pinfunction "10_10") (pintype "passive"))
    )
    (net (code "107") (name "Net-(RASPI-Pad11)") (class "Default")
      (node (ref "RASPI") (pin "11") (pinfunction "11_11") (pintype "passive"))
      (node (ref "RASPI_PAR") (pin "11") (pinfunction "11_11") (pintype "passive"))
    )
    (net (code "108") (name "Net-(RASPI-Pad12)") (class "Default")
      (node (ref "RASPI") (pin "12") (pinfunction "12_12") (pintype "passive"))
      (node (ref "RASPI_PAR") (pin "12") (pinfunction "12_12") (pintype "passive"))
    )
    (net (code "109") (name "Net-(RASPI-Pad13)") (class "Default")
      (node (ref "RASPI") (pin "13") (pinfunction "13_13") (pintype "passive"))
      (node (ref "RASPI_PAR") (pin "13") (pinfunction "13_13") (pintype "passive"))
    )
    (net (code "110") (name "Net-(RASPI-Pad14)") (class "Default")
      (node (ref "RASPI") (pin "14") (pinfunction "14_14") (pintype "passive"))
      (node (ref "RASPI_PAR") (pin "14") (pinfunction "14_14") (pintype "passive"))
    )
    (net (code "111") (name "Net-(RASPI-Pad15)") (class "Default")
      (node (ref "RASPI") (pin "15") (pinfunction "15_15") (pintype "passive"))
      (node (ref "RASPI_PAR") (pin "15") (pinfunction "15_15") (pintype "passive"))
    )
    (net (code "112") (name "Net-(RASPI-Pad16)") (class "Default")
      (node (ref "RASPI") (pin "16") (pinfunction "16_16") (pintype "passive"))
      (node (ref "RASPI_PAR") (pin "16") (pinfunction "16_16") (pintype "passive"))
    )
    (net (code "113") (name "Net-(RASPI-Pad17)") (class "Default")
      (node (ref "RASPI") (pin "17") (pinfunction "17_17") (pintype "passive"))
      (node (ref "RASPI_PAR") (pin "17") (pinfunction "17_17") (pintype "passive"))
    )
    (net (code "114") (name "Net-(RASPI-Pad18)") (class "Default")
      (node (ref "RASPI") (pin "18") (pinfunction "18_18") (pintype "passive"))
      (node (ref "RASPI_PAR") (pin "18") (pinfunction "18_18") (pintype "passive"))
    )
    (net (code "115") (name "Net-(RASPI-Pad19)") (class "Default")
      (node (ref "RASPI") (pin "19") (pinfunction "19_19") (pintype "passive"))
      (node (ref "RASPI_PAR") (pin "19") (pinfunction "19_19") (pintype "passive"))
    )
    (net (code "116") (name "Net-(RASPI-Pad20)") (class "Default")
      (node (ref "RASPI") (pin "20") (pinfunction "20_20") (pintype "passive"))
      (node (ref "RASPI_PAR") (pin "20") (pinfunction "20_20") (pintype "passive"))
    )
    (net (code "117") (name "Net-(RASPI-Pad21)") (class "Default")
      (node (ref "RASPI") (pin "21") (pinfunction "21_21") (pintype "passive"))
      (node (ref "RASPI_PAR") (pin "21") (pinfunction "21_21") (pintype "passive"))
    )
    (net (code "118") (name "Net-(RASPI-Pad22)") (class "Default")
      (node (ref "RASPI") (pin "22") (pinfunction "22_22") (pintype "passive"))
      (node (ref "RASPI_PAR") (pin "22") (pinfunction "22_22") (pintype "passive"))
    )
    (net (code "119") (name "Net-(RASPI-Pad23)") (class "Default")
      (node (ref "RASPI") (pin "23") (pinfunction "23_23") (pintype "passive"))
      (node (ref "RASPI_PAR") (pin "23") (pinfunction "23_23") (pintype "passive"))
    )
    (net (code "120") (name "Net-(RASPI-Pad24)") (class "Default")
      (node (ref "RASPI") (pin "24") (pinfunction "24_24") (pintype "passive"))
      (node (ref "RASPI_PAR") (pin "24") (pinfunction "24_24") (pintype "passive"))
    )
    (net (code "121") (name "Net-(RASPI-Pad25)") (class "Default")
      (node (ref "RASPI") (pin "25") (pinfunction "25_25") (pintype "passive"))
      (node (ref "RASPI_PAR") (pin "25") (pinfunction "25_25") (pintype "passive"))
    )
    (net (code "122") (name "Net-(RASPI-Pad26)") (class "Default")
      (node (ref "RASPI") (pin "26") (pinfunction "26_26") (pintype "passive"))
      (node (ref "RASPI_PAR") (pin "26") (pinfunction "26_26") (pintype "passive"))
    )
    (net (code "123") (name "Net-(RASPI-Pad27)") (class "Default")
      (node (ref "RASPI") (pin "27") (pinfunction "27_27") (pintype "passive"))
      (node (ref "RASPI_PAR") (pin "27") (pinfunction "27_27") (pintype "passive"))
    )
    (net (code "124") (name "Net-(RASPI-Pad28)") (class "Default")
      (node (ref "RASPI") (pin "28") (pinfunction "28_28") (pintype "passive"))
      (node (ref "RASPI_PAR") (pin "28") (pinfunction "28_28") (pintype "passive"))
    )
    (net (code "125") (name "Net-(RASPI-Pad29)") (class "Default")
      (node (ref "RASPI") (pin "29") (pinfunction "29_29") (pintype "passive"))
      (node (ref "RASPI_PAR") (pin "29") (pinfunction "29_29") (pintype "passive"))
    )
    (net (code "126") (name "Net-(RASPI-Pad30)") (class "Default")
      (node (ref "RASPI") (pin "30") (pinfunction "30_30") (pintype "passive"))
      (node (ref "RASPI_PAR") (pin "30") (pinfunction "30_30") (pintype "passive"))
    )
    (net (code "127") (name "Net-(RASPI-Pad31)") (class "Default")
      (node (ref "RASPI") (pin "31") (pinfunction "31_31") (pintype "passive"))
      (node (ref "RASPI_PAR") (pin "31") (pinfunction "31_31") (pintype "passive"))
    )
    (net (code "128") (name "Net-(RASPI-Pad32)") (class "Default")
      (node (ref "RASPI") (pin "32") (pinfunction "32_32") (pintype "passive"))
      (node (ref "RASPI_PAR") (pin "32") (pinfunction "32_32") (pintype "passive"))
    )
    (net (code "129") (name "Net-(RASPI-Pad33)") (class "Default")
      (node (ref "RASPI") (pin "33") (pinfunction "33_33") (pintype "passive"))
      (node (ref "RASPI_PAR") (pin "33") (pinfunction "33_33") (pintype "passive"))
    )
    (net (code "130") (name "Net-(RASPI-Pad34)") (class "Default")
      (node (ref "RASPI") (pin "34") (pinfunction "34_34") (pintype "passive"))
      (node (ref "RASPI_PAR") (pin "34") (pinfunction "34_34") (pintype "passive"))
    )
    (net (code "131") (name "Net-(RASPI-Pad35)") (class "Default")
      (node (ref "RASPI") (pin "35") (pinfunction "35_35") (pintype "passive"))
      (node (ref "RASPI_PAR") (pin "35") (pinfunction "35_35") (pintype "passive"))
    )
    (net (code "132") (name "Net-(RASPI-Pad36)") (class "Default")
      (node (ref "RASPI") (pin "36") (pinfunction "36_36") (pintype "passive"))
      (node (ref "RASPI_PAR") (pin "36") (pinfunction "36_36") (pintype "passive"))
    )
    (net (code "133") (name "Net-(RASPI-Pad38)") (class "Default")
      (node (ref "RASPI") (pin "38") (pinfunction "38_38") (pintype "passive"))
      (node (ref "RASPI_PAR") (pin "38") (pinfunction "38_38") (pintype "passive"))
    )
    (net (code "134") (name "Net-(RASPI-Pad40)") (class "Default")
      (node (ref "RASPI") (pin "40") (pinfunction "40_40") (pintype "passive"))
      (node (ref "RASPI_PAR") (pin "40") (pinfunction "40_40") (pintype "passive"))
    )
    (net (code "135") (name "unconnected-(CONTROL_RGB-I4-Pad14)") (class "Default")
      (node (ref "CONTROL_RGB") (pin "14") (pinfunction "I4_14") (pintype "input"))
    )
    (net (code "136") (name "unconnected-(CONTROL_RGB-K1-Pad1)") (class "Default")
      (node (ref "CONTROL_RGB") (pin "1") (pinfunction "K1_1") (pintype "passive"))
    )
    (net (code "137") (name "unconnected-(CONTROL_RGB-O4-Pad16)") (class "Default")
      (node (ref "CONTROL_RGB") (pin "16") (pinfunction "O4_16") (pintype "open_collector"))
    )
    (net (code "138") (name "unconnected-(EMCODER_6-Pad2)") (class "Default")
      (node (ref "EMCODER_6") (pin "2") (pinfunction "2_2") (pintype "passive"))
    )
    (net (code "139") (name "unconnected-(ENCODER_1-Pad2)") (class "Default")
      (node (ref "ENCODER_1") (pin "2") (pinfunction "2_2") (pintype "passive"))
    )
    (net (code "140") (name "unconnected-(ENCODER_2-Pad2)") (class "Default")
      (node (ref "ENCODER_2") (pin "2") (pinfunction "2_2") (pintype "passive"))
    )
    (net (code "141") (name "unconnected-(ENCODER_3-Pad2)") (class "Default")
      (node (ref "ENCODER_3") (pin "2") (pinfunction "2_2") (pintype "passive"))
    )
    (net (code "142") (name "unconnected-(ENCODER_4-Pad2)") (class "Default")
      (node (ref "ENCODER_4") (pin "2") (pinfunction "2_2") (pintype "passive"))
    )
    (net (code "143") (name "unconnected-(ENCODER_5-Pad2)") (class "Default")
      (node (ref "ENCODER_5") (pin "2") (pinfunction "2_2") (pintype "passive"))
    )
  )
)
